# pca63550.net
KiCad netlist of a schematic drawn in Altium Designer
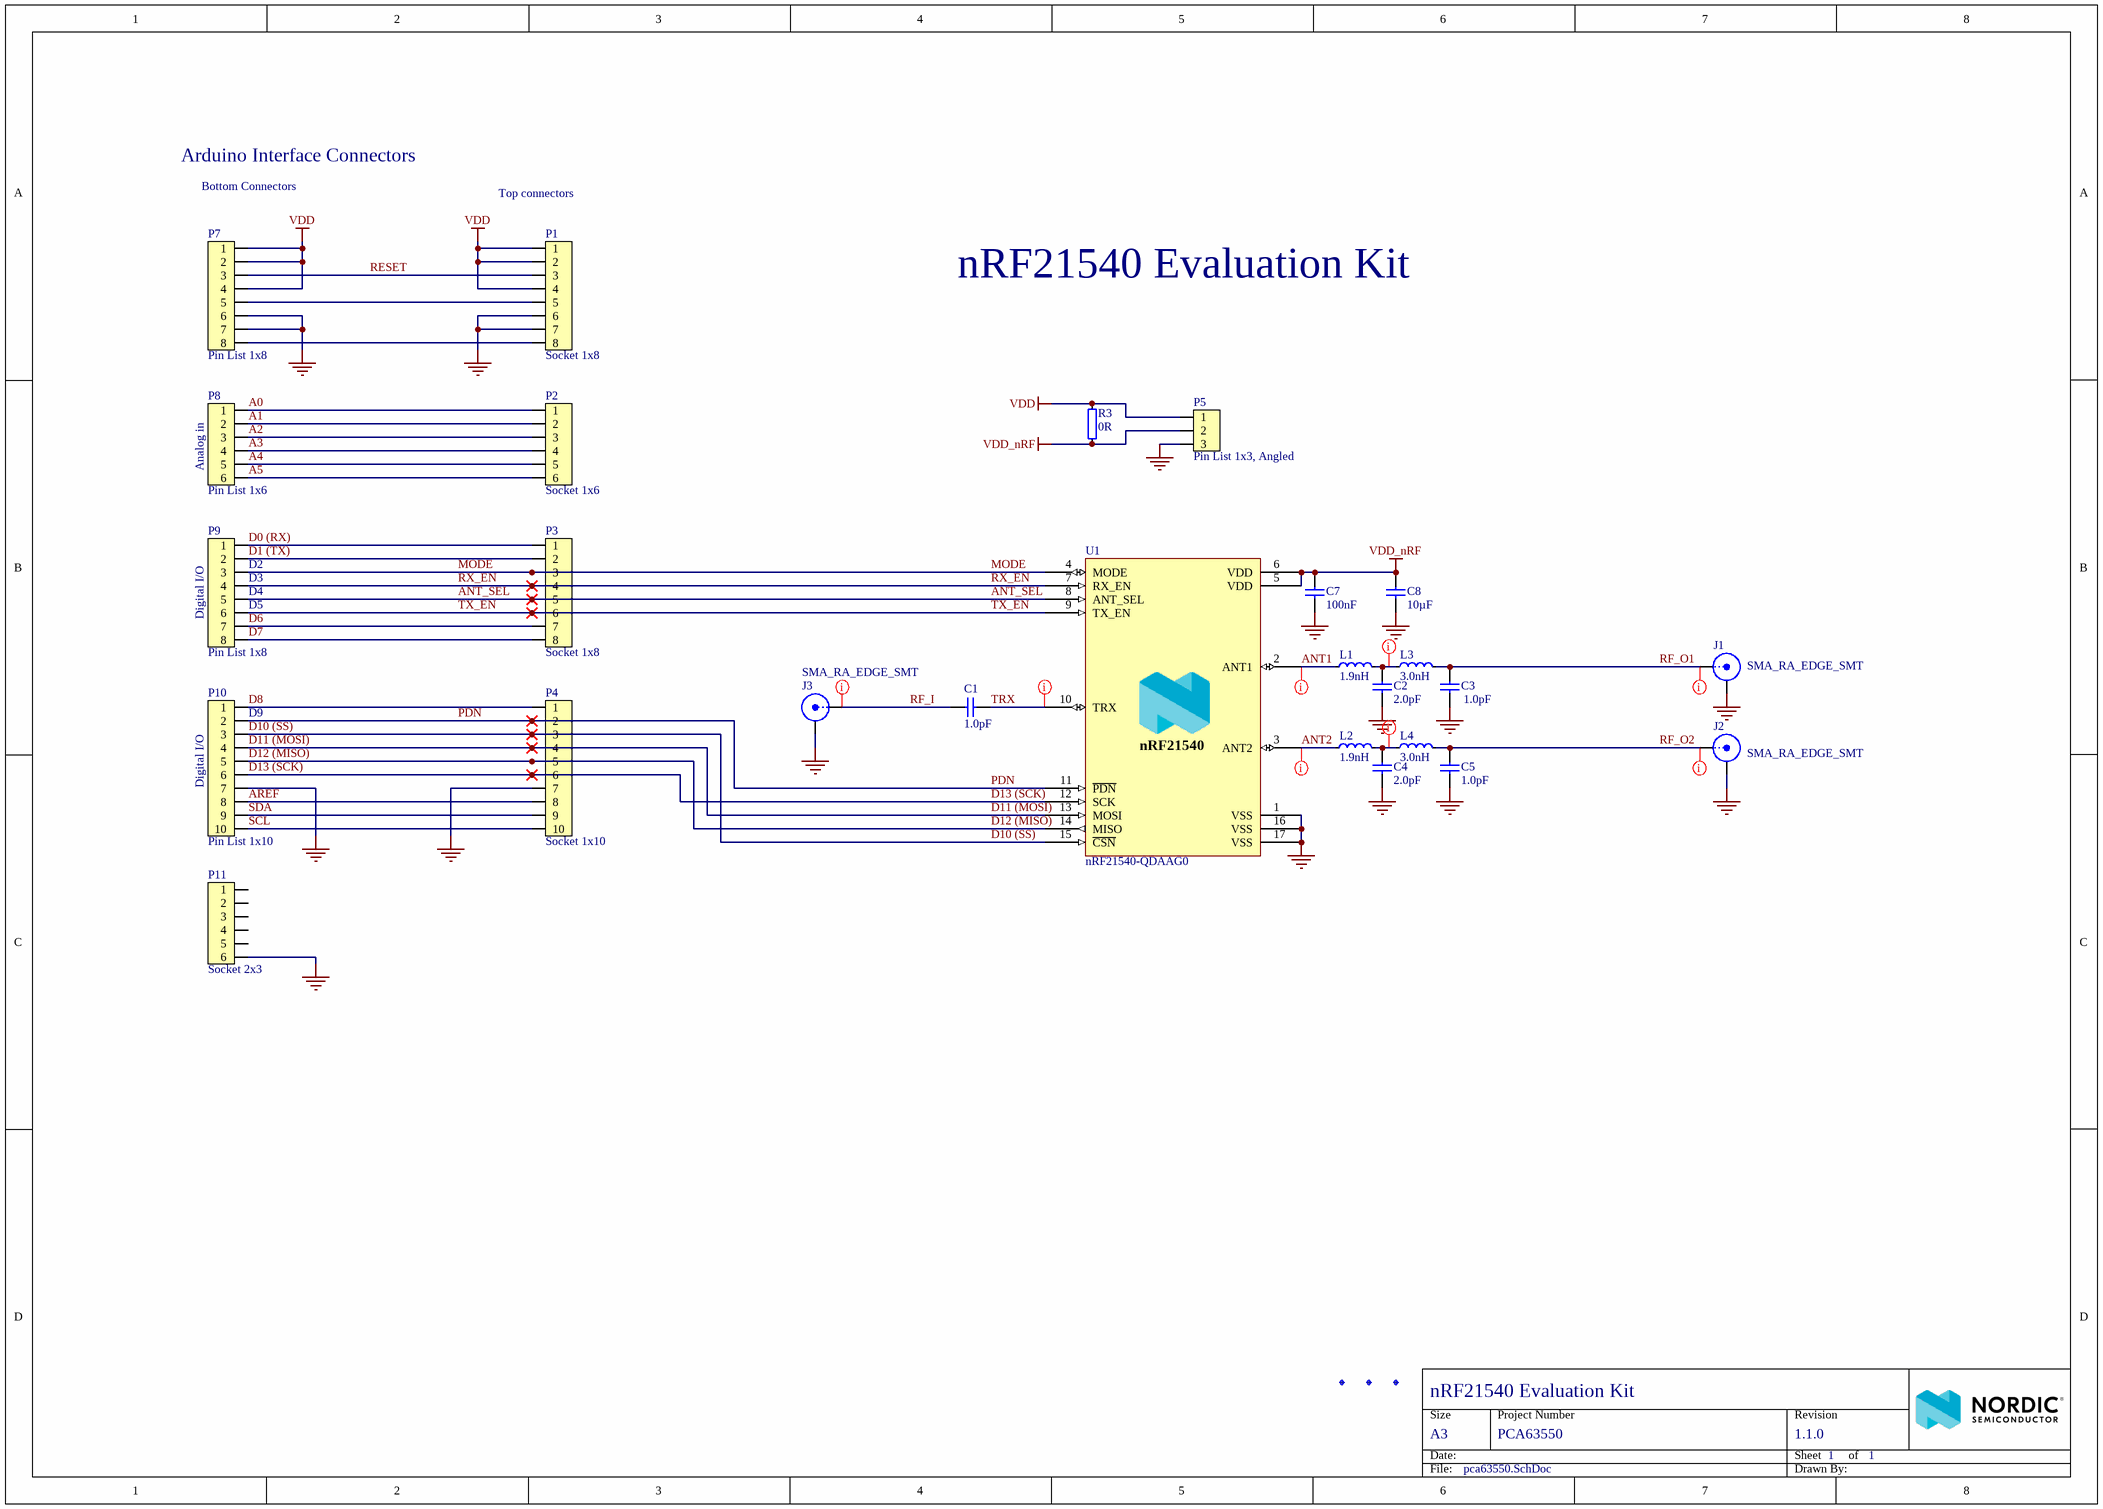
[diagram p0: pca63550.SchDoc]

(export (version "E")
  (design (tool "Eeschema 10.0.6"))
  (components
    (comp (ref "C1")
      (value "1.0pF")
      (footprint "CAPC0603X03L_C")
      (description "Capacitor, C0G, ±0.1pF, 25V")
      (fields
        (field (name "PART NUMBER") "C0201-1p0")
        (field (name "MANUFACTURER") "Murata")
        (field (name "AUTHOR") "rsk")
      )
      (libsource (lib "AltiumLib") (part "CAP"))
    )
    (comp (ref "C2")
      (value "2.0pF")
      (footprint "CAPC0603X03L_C")
      (description "Capacitor, NP0, ±0.05pF, 25V")
      (fields
        (field (name "PART NUMBER") "C0201-2.0p-HQ-Murata")
        (field (name "MANUFACTURER") "Murata")
        (field (name "AUTHOR") "rsk")
      )
      (libsource (lib "AltiumLib") (part "CAP"))
    )
    (comp (ref "C3")
      (value "1.0pF")
      (footprint "CAPC0603X03L_C")
      (description "RF Chip Cap 0201")
      (fields
        (field (name "PART NUMBER") "C0201-1.0p_RF")
        (field (name "MANUFACTURER") "N.A.")
        (field (name "AUTHOR") "rsk")
      )
      (libsource (lib "AltiumLib") (part "CAP"))
    )
    (comp (ref "C4")
      (value "2.0pF")
      (footprint "CAPC0603X03L_C")
      (description "Capacitor, NP0, ±0.05pF, 25V")
      (fields
        (field (name "PART NUMBER") "C0201-2.0p-HQ-Murata")
        (field (name "MANUFACTURER") "Murata")
        (field (name "AUTHOR") "rsk")
      )
      (libsource (lib "AltiumLib") (part "CAP"))
    )
    (comp (ref "C5")
      (value "1.0pF")
      (footprint "CAPC0603X03L_C")
      (description "RF Chip Cap 0201")
      (fields
        (field (name "PART NUMBER") "C0201-1.0p_RF")
        (field (name "MANUFACTURER") "N.A.")
        (field (name "AUTHOR") "rsk")
      )
      (libsource (lib "AltiumLib") (part "CAP"))
    )
    (comp (ref "C7")
      (value "100nF")
      (footprint "CAPC0603X03L_C")
      (description "Capacitor, X5R, ±10%")
      (fields
        (field (name "PART NUMBER") "C0201-100n")
        (field (name "MANUFACTURER") "N.A.")
        (field (name "AUTHOR") "rsk")
      )
      (libsource (lib "AltiumLib") (part "CAP"))
    )
    (comp (ref "C8")
      (value "10µF")
      (footprint "CAPC1608X06L")
      (description "Capacitor, X5R, ±20%")
      (fields
        (field (name "PART NUMBER") "C0603-10µ")
        (field (name "MANUFACTURER") "N.A.")
        (field (name "AUTHOR") "rsk")
      )
      (libsource (lib "AltiumLib") (part "CAP"))
    )
    (comp (ref "Fid1")
      (value "Fiducial mark")
      (footprint "Fiducial")
      (description "Fiducial Mark")
      (fields
        (field (name "PART NUMBER") "Fid-Mark")
        (field (name "MANUFACTURER") "N.A.")
        (field (name "AUTHOR") "rsk")
      )
      (libsource (lib "AltiumLib") (part "Fiducial"))
    )
    (comp (ref "Fid2")
      (value "Fiducial mark")
      (footprint "Fiducial")
      (description "Fiducial Mark")
      (fields
        (field (name "PART NUMBER") "Fid-Mark")
        (field (name "MANUFACTURER") "N.A.")
        (field (name "AUTHOR") "rsk")
      )
      (libsource (lib "AltiumLib") (part "Fiducial"))
    )
    (comp (ref "Fid3")
      (value "Fiducial mark")
      (footprint "Fiducial")
      (description "Fiducial Mark")
      (fields
        (field (name "PART NUMBER") "Fid-Mark")
        (field (name "MANUFACTURER") "N.A.")
        (field (name "AUTHOR") "rsk")
      )
      (libsource (lib "AltiumLib") (part "Fiducial"))
    )
    (comp (ref "J1")
      (value "SMA_2081005-1")
      (footprint "SMA_2081005-1")
      (description "SMA, Female, Right Angle, TH/SMT, 50Ohm, Board Edge")
      (fields
        (field (name "PART NUMBER") "SMA_RA_EDGE_SMT")
        (field (name "MANUFACTURER") "CompuPack")
        (field (name "MANUFACTURER PART NUMBER") "ARFRBE22029-GGP")
        (field (name "AUTHOR") "rsk")
      )
      (libsource (lib "AltiumLib") (part "SMA"))
    )
    (comp (ref "J2")
      (value "SMA_2081005-1")
      (footprint "SMA_2081005-1")
      (description "SMA, Female, Right Angle, TH/SMT, 50Ohm, Board Edge")
      (fields
        (field (name "PART NUMBER") "SMA_RA_EDGE_SMT")
        (field (name "MANUFACTURER") "CompuPack")
        (field (name "MANUFACTURER PART NUMBER") "ARFRBE22029-GGP")
        (field (name "AUTHOR") "rsk")
      )
      (libsource (lib "AltiumLib") (part "SMA"))
    )
    (comp (ref "J3")
      (value "SMA_2081005-1")
      (footprint "SMA_2081005-1")
      (description "SMA, Female, Right Angle, TH/SMT, 50Ohm, Board Edge")
      (fields
        (field (name "PART NUMBER") "SMA_RA_EDGE_SMT")
        (field (name "MANUFACTURER") "CompuPack")
        (field (name "MANUFACTURER PART NUMBER") "ARFRBE22029-GGP")
        (field (name "AUTHOR") "rsk")
      )
      (libsource (lib "AltiumLib") (part "SMA"))
    )
    (comp (ref "L1")
      (value "1.9nH")
      (footprint "INDC0603X03L_C")
      (description "Inductor, 600mA, ±0.1ｎH, 120mOhm")
      (fields
        (field (name "PART NUMBER") "L0201-1n9-HQ-Murata")
        (field (name "MANUFACTURER") "Murata")
        (field (name "AUTHOR") "rsk")
      )
      (libsource (lib "AltiumLib") (part "IND"))
    )
    (comp (ref "L2")
      (value "1.9nH")
      (footprint "INDC0603X03L_C")
      (description "Inductor, 600mA, ±0.1ｎH, 120mOhm")
      (fields
        (field (name "PART NUMBER") "L0201-1n9-HQ-Murata")
        (field (name "MANUFACTURER") "Murata")
        (field (name "AUTHOR") "rsk")
      )
      (libsource (lib "AltiumLib") (part "IND"))
    )
    (comp (ref "L3")
      (value "3.0nH")
      (footprint "INDC0603X03L_C")
      (description "Inductor, 600mA, ±0.1ｎH, 120mOhm")
      (fields
        (field (name "PART NUMBER") "L0201-3n0-HQ-Murata")
        (field (name "MANUFACTURER") "Murata")
        (field (name "AUTHOR") "rsk")
      )
      (libsource (lib "AltiumLib") (part "IND"))
    )
    (comp (ref "L4")
      (value "3.0nH")
      (footprint "INDC0603X03L_C")
      (description "Inductor, 600mA, ±0.1ｎH, 120mOhm")
      (fields
        (field (name "PART NUMBER") "L0201-3n0-HQ-Murata")
        (field (name "MANUFACTURER") "Murata")
        (field (name "AUTHOR") "rsk")
      )
      (libsource (lib "AltiumLib") (part "IND"))
    )
    (comp (ref "P1")
      (value "Socket 1x8")
      (footprint "SOCKET_1x8_SMD")
      (description "Socket 1x8, 2.54mm (100mil), SMD")
      (fields
        (field (name "PART NUMBER") "Socket 1x8 SMD")
        (field (name "MANUFACTURER") "W-CON")
        (field (name "AUTHOR") "rsk")
      )
      (libsource (lib "AltiumLib") (part "CONN-8"))
    )
    (comp (ref "P2")
      (value "Socket 1x6")
      (footprint "SOCKET_1x6_SMD")
      (description "Socket 1x6, 2.54mm (100mil), SMD")
      (fields
        (field (name "PART NUMBER") "Socket 1x6 SMD")
        (field (name "MANUFACTURER") "W-CON")
        (field (name "AUTHOR") "rsk")
      )
      (libsource (lib "") (part "CONN-6_1"))
    )
    (comp (ref "P3")
      (value "Socket 1x8")
      (footprint "SOCKET_1x8_SMD")
      (description "Socket 1x8, 2.54mm (100mil), SMD")
      (fields
        (field (name "PART NUMBER") "Socket 1x8 SMD")
        (field (name "MANUFACTURER") "W-CON")
        (field (name "AUTHOR") "rsk")
      )
      (libsource (lib "AltiumLib") (part "CONN-8"))
    )
    (comp (ref "P4")
      (value "Socket 1x10")
      (footprint "SOCKET_1x10_SMD")
      (description "Socket 1x10, 2.54mm (100mil), SMD")
      (fields
        (field (name "PART NUMBER") "Socket 1x10 SMD")
        (field (name "MANUFACTURER") "W-CON")
        (field (name "AUTHOR") "rsk")
      )
      (libsource (lib "") (part "CONN-10_1"))
    )
    (comp (ref "P5")
      (value "Pin List 1x3, Angled")
      (footprint "LIST_ANG_1x3-SMD-2.54MM")
      (description "Pin List 1x3, 2.54mm (100mil), Right Angled, SMD")
      (fields
        (field (name "PART NUMBER") "Pin List Ang 1x3 SMD, 2.54mm")
        (field (name "MANUFACTURER") "W-CON")
        (field (name "AUTHOR") "rsk")
      )
      (libsource (lib "AltiumLib") (part "CONN-3"))
    )
    (comp (ref "P7")
      (value "Pin List 1x8")
      (footprint "LIST_1x8_SMD")
      (description "Pin List 1x8, 2.54mm (100mil), SMD")
      (fields
        (field (name "PART NUMBER") "Pin List 1x8 SMD")
        (field (name "MANUFACTURER") "W-CON")
        (field (name "AUTHOR") "rsk")
      )
      (libsource (lib "") (part "CONN-8_1"))
    )
    (comp (ref "P8")
      (value "Pin List 1x6")
      (footprint "LIST_1x6_SMD")
      (description "Pin List 1x6, 2.54mm (100mil), SMD")
      (fields
        (field (name "PART NUMBER") "Pin List 1x6 SMD")
        (field (name "MANUFACTURER") "W-CON")
        (field (name "AUTHOR") "rsk")
      )
      (libsource (lib "AltiumLib") (part "CONN-6"))
    )
    (comp (ref "P9")
      (value "Pin List 1x8")
      (footprint "LIST_1x8_SMD")
      (description "Pin List 1x8, 2.54mm (100mil), SMD")
      (fields
        (field (name "PART NUMBER") "Pin List 1x8 SMD")
        (field (name "MANUFACTURER") "W-CON")
        (field (name "AUTHOR") "rsk")
      )
      (libsource (lib "") (part "CONN-8_1"))
    )
    (comp (ref "P10")
      (value "Pin List 1x10")
      (footprint "LIST_1x10_SMD")
      (description "Pin List 1x10, 2.54mm (100mil), SMD")
      (fields
        (field (name "PART NUMBER") "Pin List 1x10 SMD")
        (field (name "MANUFACTURER") "W-CON")
        (field (name "AUTHOR") "rsk")
      )
      (libsource (lib "AltiumLib") (part "CONN-10"))
    )
    (comp (ref "P11")
      (value "Socket 2x3")
      (footprint "SOCKET_2x3_SMD-2.54mm-bottom")
      (description "Socket 2x3, 2.54mm (100mil), SMD")
      (fields
        (field (name "PART NUMBER") "Socket 2x3 SMD Bottom")
        (field (name "MANUFACTURER") "W-CON")
        (field (name "AUTHOR") "rsk")
      )
      (libsource (lib "AltiumLib") (part "CONN-6"))
    )
    (comp (ref "R3")
      (value "0R")
      (footprint "RESC1005X04L")
      (description "Resistor, ±5%, 0.063W")
      (fields
        (field (name "PART NUMBER") "R0402-0R")
        (field (name "MANUFACTURER") "N.A.")
        (field (name "AUTHOR") "rsk")
      )
      (libsource (lib "AltiumLib") (part "RES"))
    )
    (comp (ref "U1")
      (value "nRF21540-QDAAG0")
      (footprint "QFN65P400X400X65_HS-17N")
      (description "Radio front-end / range extender for 2.4GHz")
      (fields (field (name "MANUFACTURER") "Nordic Semiconductor") (field (name "AUTHOR") "hany"))
      (libsource (lib "AltiumLib") (part "nRF21540-QDAA"))
    )
  )
  (nets
    (net (code "1") (name "/A0") (class "Default")
      (node (ref "P2") (pin "1") (pinfunction "1_1") (pintype "passive"))
      (node (ref "P8") (pin "1") (pinfunction "1_1") (pintype "passive"))
    )
    (net (code "2") (name "/A1") (class "Default")
      (node (ref "P2") (pin "2") (pinfunction "2_2") (pintype "passive"))
      (node (ref "P8") (pin "2") (pinfunction "2_2") (pintype "passive"))
    )
    (net (code "3") (name "/A2") (class "Default")
      (node (ref "P2") (pin "3") (pinfunction "3_3") (pintype "passive"))
      (node (ref "P8") (pin "3") (pinfunction "3_3") (pintype "passive"))
    )
    (net (code "4") (name "/A3") (class "Default")
      (node (ref "P2") (pin "4") (pinfunction "4_4") (pintype "passive"))
      (node (ref "P8") (pin "4") (pinfunction "4_4") (pintype "passive"))
    )
    (net (code "5") (name "/A4") (class "Default")
      (node (ref "P2") (pin "5") (pinfunction "5_5") (pintype "passive"))
      (node (ref "P8") (pin "5") (pinfunction "5_5") (pintype "passive"))
    )
    (net (code "6") (name "/A5") (class "Default")
      (node (ref "P2") (pin "6") (pinfunction "6_6") (pintype "passive"))
      (node (ref "P8") (pin "6") (pinfunction "6_6") (pintype "passive"))
    )
    (net (code "7") (name "/ANT1") (class "Default")
      (node (ref "L1") (pin "1") (pinfunction "1_1") (pintype "passive"))
      (node (ref "U1") (pin "2") (pinfunction "ANT1_2") (pintype "bidirectional"))
    )
    (net (code "8") (name "/ANT2") (class "Default")
      (node (ref "L2") (pin "1") (pinfunction "1_1") (pintype "passive"))
      (node (ref "U1") (pin "3") (pinfunction "ANT2_3") (pintype "bidirectional"))
    )
    (net (code "9") (name "/ANT_SEL") (class "Default")
      (node (ref "P3") (pin "5") (pinfunction "5_5") (pintype "passive"))
      (node (ref "P9") (pin "5") (pinfunction "5_5") (pintype "passive"))
      (node (ref "U1") (pin "8") (pinfunction "ANT_SEL_8") (pintype "input"))
    )
    (net (code "10") (name "/AREF") (class "Default")
      (node (ref "P10") (pin "8") (pinfunction "8_8") (pintype "passive"))
      (node (ref "P4") (pin "8") (pinfunction "8_8") (pintype "passive"))
    )
    (net (code "11") (name "/D0 (RX)") (class "Default")
      (node (ref "P3") (pin "1") (pinfunction "1_1") (pintype "passive"))
      (node (ref "P9") (pin "1") (pinfunction "1_1") (pintype "passive"))
    )
    (net (code "12") (name "/D1 (TX)") (class "Default")
      (node (ref "P3") (pin "2") (pinfunction "2_2") (pintype "passive"))
      (node (ref "P9") (pin "2") (pinfunction "2_2") (pintype "passive"))
    )
    (net (code "13") (name "/D6") (class "Default")
      (node (ref "P3") (pin "7") (pinfunction "7_7") (pintype "passive"))
      (node (ref "P9") (pin "7") (pinfunction "7_7") (pintype "passive"))
    )
    (net (code "14") (name "/D7") (class "Default")
      (node (ref "P3") (pin "8") (pinfunction "8_8") (pintype "passive"))
      (node (ref "P9") (pin "8") (pinfunction "8_8") (pintype "passive"))
    )
    (net (code "15") (name "/D8") (class "Default")
      (node (ref "P10") (pin "1") (pinfunction "1_1") (pintype "passive"))
      (node (ref "P4") (pin "1") (pinfunction "1_1") (pintype "passive"))
    )
    (net (code "16") (name "/D10 (SS)") (class "Default")
      (node (ref "P10") (pin "3") (pinfunction "3_3") (pintype "passive"))
      (node (ref "P4") (pin "3") (pinfunction "3_3") (pintype "passive"))
      (node (ref "U1") (pin "15") (pinfunction "~{CSN}_15") (pintype "input"))
    )
    (net (code "17") (name "/D11 (MOSI)") (class "Default")
      (node (ref "P10") (pin "4") (pinfunction "4_4") (pintype "passive"))
      (node (ref "P4") (pin "4") (pinfunction "4_4") (pintype "passive"))
      (node (ref "U1") (pin "13") (pinfunction "MOSI_13") (pintype "input"))
    )
    (net (code "18") (name "/D12 (MISO)") (class "Default")
      (node (ref "P10") (pin "5") (pinfunction "5_5") (pintype "passive"))
      (node (ref "P4") (pin "5") (pinfunction "5_5") (pintype "passive"))
      (node (ref "U1") (pin "14") (pinfunction "MISO_14") (pintype "output"))
    )
    (net (code "19") (name "/D13 (SCK)") (class "Default")
      (node (ref "P10") (pin "6") (pinfunction "6_6") (pintype "passive"))
      (node (ref "P4") (pin "6") (pinfunction "6_6") (pintype "passive"))
      (node (ref "U1") (pin "12") (pinfunction "SCK_12") (pintype "input"))
    )
    (net (code "20") (name "/MODE") (class "Default")
      (node (ref "P3") (pin "3") (pinfunction "3_3") (pintype "passive"))
      (node (ref "P9") (pin "3") (pinfunction "3_3") (pintype "passive"))
      (node (ref "U1") (pin "4") (pinfunction "MODE_4") (pintype "bidirectional"))
    )
    (net (code "21") (name "/PDN") (class "Default")
      (node (ref "P10") (pin "2") (pinfunction "2_2") (pintype "passive"))
      (node (ref "P4") (pin "2") (pinfunction "2_2") (pintype "passive"))
      (node (ref "U1") (pin "11") (pinfunction "~{PDN}_11") (pintype "input"))
    )
    (net (code "22") (name "/RESET") (class "Default")
      (node (ref "P1") (pin "3") (pinfunction "3_3") (pintype "passive"))
      (node (ref "P7") (pin "3") (pinfunction "3_3") (pintype "passive"))
    )
    (net (code "23") (name "/RF_I") (class "Default")
      (node (ref "C1") (pin "1") (pinfunction "1_1") (pintype "passive"))
      (node (ref "J3") (pin "1") (pinfunction "X_1") (pintype "passive"))
    )
    (net (code "24") (name "/RF_O1") (class "Default")
      (node (ref "C3") (pin "2") (pinfunction "2_2") (pintype "passive"))
      (node (ref "J1") (pin "1") (pinfunction "X_1") (pintype "passive"))
      (node (ref "L3") (pin "2") (pinfunction "2_2") (pintype "passive"))
    )
    (net (code "25") (name "/RF_O2") (class "Default")
      (node (ref "C5") (pin "2") (pinfunction "2_2") (pintype "passive"))
      (node (ref "J2") (pin "1") (pinfunction "X_1") (pintype "passive"))
      (node (ref "L4") (pin "2") (pinfunction "2_2") (pintype "passive"))
    )
    (net (code "26") (name "/RX_EN") (class "Default")
      (node (ref "P3") (pin "4") (pinfunction "4_4") (pintype "passive"))
      (node (ref "P9") (pin "4") (pinfunction "4_4") (pintype "passive"))
      (node (ref "U1") (pin "7") (pinfunction "RX_EN_7") (pintype "input"))
    )
    (net (code "27") (name "/SCL") (class "Default")
      (node (ref "P10") (pin "10") (pinfunction "10_10") (pintype "passive"))
      (node (ref "P4") (pin "10") (pinfunction "10_10") (pintype "passive"))
    )
    (net (code "28") (name "/SDA") (class "Default")
      (node (ref "P10") (pin "9") (pinfunction "9_9") (pintype "passive"))
      (node (ref "P4") (pin "9") (pinfunction "9_9") (pintype "passive"))
    )
    (net (code "29") (name "/TRX") (class "Default")
      (node (ref "C1") (pin "2") (pinfunction "2_2") (pintype "passive"))
      (node (ref "U1") (pin "10") (pinfunction "TRX_10") (pintype "bidirectional"))
    )
    (net (code "30") (name "/TX_EN") (class "Default")
      (node (ref "P3") (pin "6") (pinfunction "6_6") (pintype "passive"))
      (node (ref "P9") (pin "6") (pinfunction "6_6") (pintype "passive"))
      (node (ref "U1") (pin "9") (pinfunction "TX_EN_9") (pintype "input"))
    )
    (net (code "31") (name "GND") (class "Default")
      (node (ref "C2") (pin "1") (pinfunction "1_1") (pintype "passive"))
      (node (ref "C3") (pin "1") (pinfunction "1_1") (pintype "passive"))
      (node (ref "C4") (pin "1") (pinfunction "1_1") (pintype "passive"))
      (node (ref "C5") (pin "1") (pinfunction "1_1") (pintype "passive"))
      (node (ref "C7") (pin "1") (pinfunction "1_1") (pintype "passive"))
      (node (ref "C8") (pin "1") (pinfunction "1_1") (pintype "passive"))
      (node (ref "J1") (pin "2") (pinfunction "Y_2") (pintype "passive"))
      (node (ref "J2") (pin "2") (pinfunction "Y_2") (pintype "passive"))
      (node (ref "J3") (pin "2") (pinfunction "Y_2") (pintype "passive"))
      (node (ref "P1") (pin "6") (pinfunction "6_6") (pintype "passive"))
      (node (ref "P1") (pin "7") (pinfunction "7_7") (pintype "passive"))
      (node (ref "P10") (pin "7") (pinfunction "7_7") (pintype "passive"))
      (node (ref "P11") (pin "6") (pinfunction "6_6") (pintype "passive"))
      (node (ref "P4") (pin "7") (pinfunction "7_7") (pintype "passive"))
      (node (ref "P5") (pin "3") (pinfunction "3_3") (pintype "passive"))
      (node (ref "P7") (pin "6") (pinfunction "6_6") (pintype "passive"))
      (node (ref "P7") (pin "7") (pinfunction "7_7") (pintype "passive"))
      (node (ref "U1") (pin "1") (pinfunction "VSS_1") (pintype "power_in"))
      (node (ref "U1") (pin "16") (pinfunction "VSS_16") (pintype "power_in"))
      (node (ref "U1") (pin "17") (pinfunction "VSS_17") (pintype "power_in"))
    )
    (net (code "32") (name "Net-(C2-Pad2)") (class "Default")
      (node (ref "C2") (pin "2") (pinfunction "2_2") (pintype "passive"))
      (node (ref "L1") (pin "2") (pinfunction "2_2") (pintype "passive"))
      (node (ref "L3") (pin "1") (pinfunction "1_1") (pintype "passive"))
    )
    (net (code "33") (name "Net-(C4-Pad2)") (class "Default")
      (node (ref "C4") (pin "2") (pinfunction "2_2") (pintype "passive"))
      (node (ref "L2") (pin "2") (pinfunction "2_2") (pintype "passive"))
      (node (ref "L4") (pin "1") (pinfunction "1_1") (pintype "passive"))
    )
    (net (code "34") (name "Net-(P1-Pad5)") (class "Default")
      (node (ref "P1") (pin "5") (pinfunction "5_5") (pintype "passive"))
      (node (ref "P7") (pin "5") (pinfunction "5_5") (pintype "passive"))
    )
    (net (code "35") (name "Net-(P1-Pad8)") (class "Default")
      (node (ref "P1") (pin "8") (pinfunction "8_8") (pintype "passive"))
      (node (ref "P7") (pin "8") (pinfunction "8_8") (pintype "passive"))
    )
    (net (code "36") (name "VDD") (class "Default")
      (node (ref "P1") (pin "1") (pinfunction "1_1") (pintype "passive"))
      (node (ref "P1") (pin "2") (pinfunction "2_2") (pintype "passive"))
      (node (ref "P1") (pin "4") (pinfunction "4_4") (pintype "passive"))
      (node (ref "P5") (pin "1") (pinfunction "1_1") (pintype "passive"))
      (node (ref "P7") (pin "1") (pinfunction "1_1") (pintype "passive"))
      (node (ref "P7") (pin "2") (pinfunction "2_2") (pintype "passive"))
      (node (ref "P7") (pin "4") (pinfunction "4_4") (pintype "passive"))
      (node (ref "R3") (pin "2") (pinfunction "2_2") (pintype "passive"))
    )
    (net (code "37") (name "VDD_nRF") (class "Default")
      (node (ref "C7") (pin "2") (pinfunction "2_2") (pintype "passive"))
      (node (ref "C8") (pin "2") (pinfunction "2_2") (pintype "passive"))
      (node (ref "P5") (pin "2") (pinfunction "2_2") (pintype "passive"))
      (node (ref "R3") (pin "1") (pinfunction "1_1") (pintype "passive"))
      (node (ref "U1") (pin "5") (pinfunction "VDD_5") (pintype "power_in"))
      (node (ref "U1") (pin "6") (pinfunction "VDD_6") (pintype "power_in"))
    )
    (net (code "38") (name "unconnected-(P11-Pad1)") (class "Default")
      (node (ref "P11") (pin "1") (pinfunction "1_1") (pintype "passive"))
    )
    (net (code "39") (name "unconnected-(P11-Pad2)") (class "Default")
      (node (ref "P11") (pin "2") (pinfunction "2_2") (pintype "passive"))
    )
    (net (code "40") (name "unconnected-(P11-Pad3)") (class "Default")
      (node (ref "P11") (pin "3") (pinfunction "3_3") (pintype "passive"))
    )
    (net (code "41") (name "unconnected-(P11-Pad4)") (class "Default")
      (node (ref "P11") (pin "4") (pinfunction "4_4") (pintype "passive"))
    )
    (net (code "42") (name "unconnected-(P11-Pad5)") (class "Default")
      (node (ref "P11") (pin "5") (pinfunction "5_5") (pintype "passive"))
    )
  )
)
